# Brightness_Sensor_Schematic.net
KiCad netlist of a schematic drawn in Altium Designer
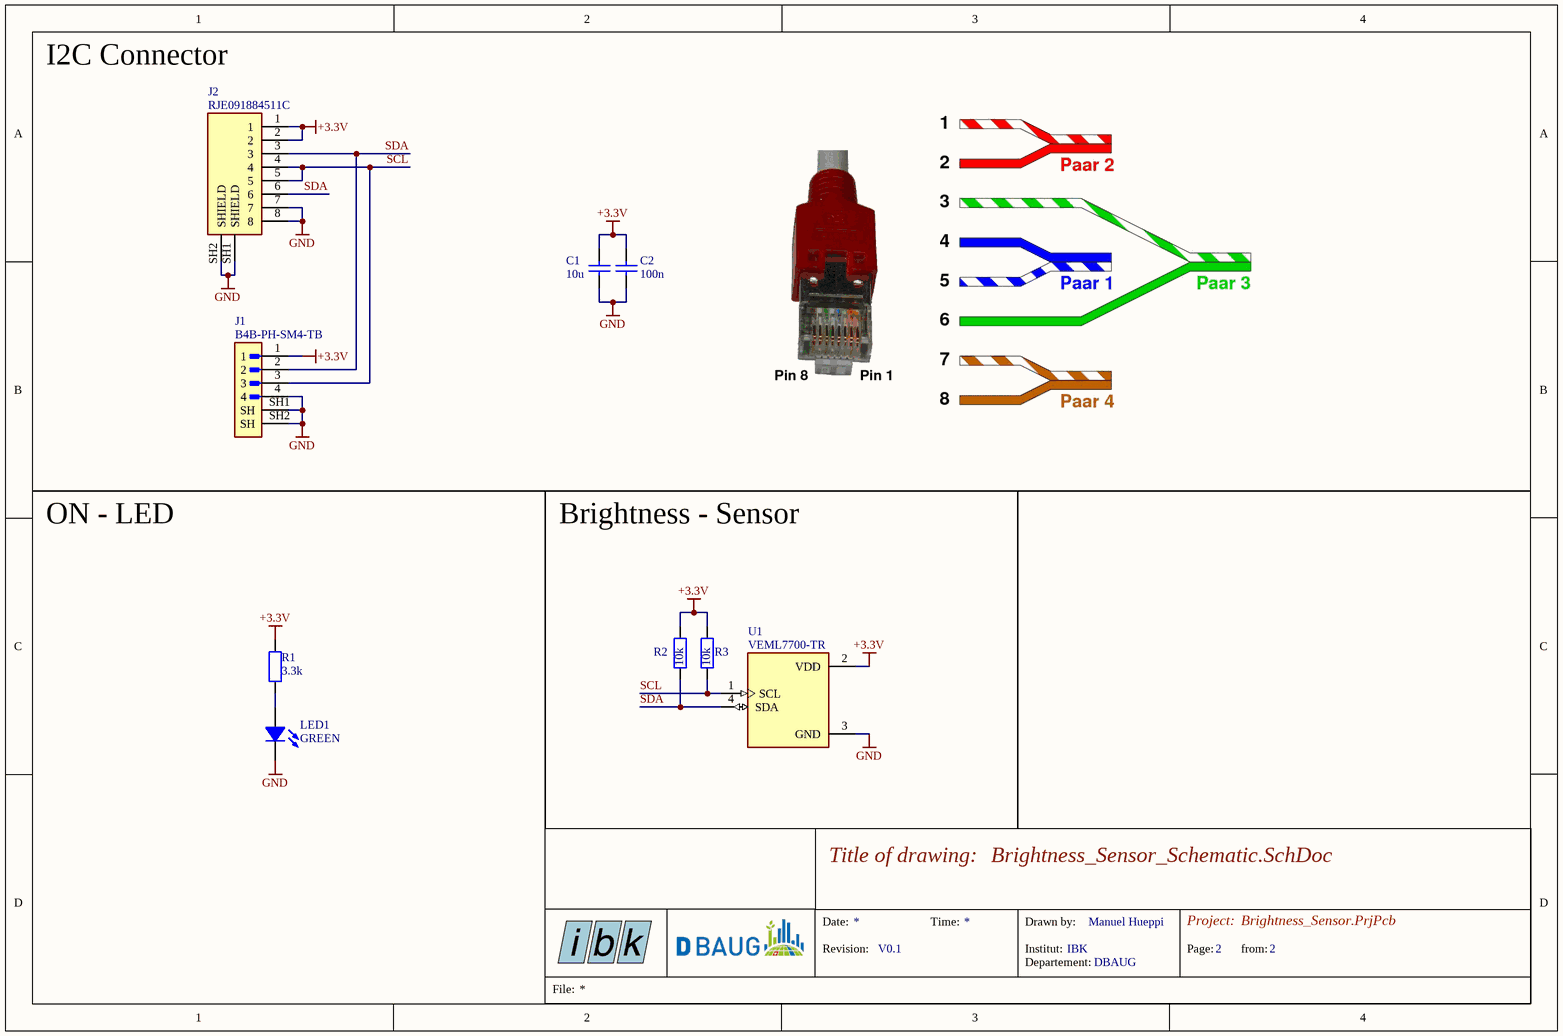
[diagram p0: Brightness_Sensor_Schematic.SchDoc]

(export (version "E")
  (design (tool "Eeschema 10.0.6"))
  (components
    (comp (ref "C1")
      (value "10u")
      (footprint "PCB_Altium_Library_Manuel:0603_CAPACITOR")
      (description "0603")
      (libsource (lib "Schematic_Altium_Library_Manuel") (part "Capacitor"))
    )
    (comp (ref "C2")
      (value "100n")
      (footprint "PCB_Altium_Library_Manuel:0603_CAPACITOR")
      (description "0603")
      (libsource (lib "Schematic_Altium_Library_Manuel") (part "Capacitor"))
    )
    (comp (ref "J1")
      (value "B4B-PH-SM4-TB")
      (footprint "PCB_Altium_Library_Manuel:Connector_SMD")
      (description "CONN HEADER SMD 4POS 2MM.")
      (libsource (lib "Schematic_Altium_Library_Manuel") (part "Connector_SMD_Small_Symbol"))
    )
    (comp (ref "J2")
      (value "RJE091884511C")
      (footprint "PCB_Altium_Library_Manuel:RJ45")
      (description "Jack Modular Connector 8p8c (RJ45, Ethernet) 90Â° Angle (Right) Shielded Cat3.")
      (fields (field (name "MF") "Amphenol ICC (Commercial Products)"))
      (libsource (lib "Schematic_Altium_Library_Manuel") (part "RJ45"))
    )
    (comp (ref "LED1")
      (value "GREEN")
      (footprint "PCB_Altium_Library_Manuel:LED_0603, GREEN")
      (description "LED 0603, Green, 3.2 V, 20 mA, 430 mcd")
      (libsource (lib "Schematic_Altium_Library_Manuel") (part "LED_0603, GREEN"))
    )
    (comp (ref "R1")
      (value "3.3k")
      (footprint "PCB_Altium_Library_Manuel:0603_Resistor")
      (description "0603")
      (libsource (lib "Schematic_Altium_Library_Manuel") (part "Resistor"))
    )
    (comp (ref "R2")
      (value "10k")
      (footprint "PCB_Altium_Library_Manuel:0603_Resistor")
      (description "0603")
      (libsource (lib "Schematic_Altium_Library_Manuel") (part "Resistor"))
    )
    (comp (ref "R3")
      (value "10k")
      (footprint "PCB_Altium_Library_Manuel:0603_Resistor")
      (description "0603")
      (libsource (lib "Schematic_Altium_Library_Manuel") (part "Resistor"))
    )
    (comp (ref "U1")
      (value "VEML7700-TR")
      (footprint "PCB_Altium_Library_Manuel:Brightness_Sensor")
      (description "SENSOR OPT 545NMAMB 4 SMD J LEAD.")
      (libsource (lib "Schematic_Altium_Library_Manuel") (part "Brightness_Sensor"))
    )
  )
  (nets
    (net (code "1") (name "+3.3V") (class "Default")
      (node (ref "C1") (pin "2") (pinfunction "2_2") (pintype "passive"))
      (node (ref "C2") (pin "2") (pinfunction "2_2") (pintype "passive"))
      (node (ref "J1") (pin "1") (pinfunction "1_1") (pintype "passive"))
      (node (ref "J2") (pin "1") (pinfunction "1_1") (pintype "passive"))
      (node (ref "J2") (pin "2") (pinfunction "2_2") (pintype "passive"))
      (node (ref "R1") (pin "2") (pinfunction "2_2") (pintype "passive"))
      (node (ref "R2") (pin "2") (pinfunction "2_2") (pintype "passive"))
      (node (ref "R3") (pin "2") (pinfunction "2_2") (pintype "passive"))
      (node (ref "U1") (pin "2") (pinfunction "VDD_2") (pintype "power_in"))
    )
    (net (code "2") (name "/SCL") (class "Default")
      (node (ref "J1") (pin "3") (pinfunction "3_3") (pintype "passive"))
      (node (ref "J2") (pin "4") (pinfunction "4_4") (pintype "passive"))
      (node (ref "J2") (pin "5") (pinfunction "5_5") (pintype "passive"))
      (node (ref "R3") (pin "1") (pinfunction "1_1") (pintype "passive"))
      (node (ref "U1") (pin "1") (pinfunction "SCL_1") (pintype "input"))
    )
    (net (code "3") (name "/SDA") (class "Default")
      (node (ref "J1") (pin "2") (pinfunction "2_2") (pintype "passive"))
      (node (ref "J2") (pin "3") (pinfunction "3_3") (pintype "passive"))
      (node (ref "J2") (pin "6") (pinfunction "6_6") (pintype "passive"))
      (node (ref "R2") (pin "1") (pinfunction "1_1") (pintype "passive"))
      (node (ref "U1") (pin "4") (pinfunction "SDA_4") (pintype "bidirectional"))
    )
    (net (code "4") (name "GND") (class "Default")
      (node (ref "C1") (pin "1") (pinfunction "1_1") (pintype "passive"))
      (node (ref "C2") (pin "1") (pinfunction "1_1") (pintype "passive"))
      (node (ref "J1") (pin "4") (pinfunction "4_4") (pintype "passive"))
      (node (ref "J1") (pin "SH1") (pinfunction "SH_SH1") (pintype "passive"))
      (node (ref "J1") (pin "SH2") (pinfunction "SH_SH2") (pintype "passive"))
      (node (ref "J2") (pin "7") (pinfunction "7_7") (pintype "passive"))
      (node (ref "J2") (pin "8") (pinfunction "8_8") (pintype "passive"))
      (node (ref "J2") (pin "SH1") (pinfunction "SHIELD_SH1") (pintype "passive"))
      (node (ref "J2") (pin "SH2") (pinfunction "SHIELD_SH2") (pintype "passive"))
      (node (ref "LED1") (pin "K") (pinfunction "K_K") (pintype "passive"))
      (node (ref "U1") (pin "3") (pinfunction "GND_3") (pintype "power_in"))
    )
    (net (code "5") (name "Net-(LED1-PadA)") (class "Default")
      (node (ref "LED1") (pin "A") (pinfunction "A_A") (pintype "passive"))
      (node (ref "R1") (pin "1") (pinfunction "1_1") (pintype "passive"))
    )
  )
)
